# Main.net
KiCad netlist of a schematic drawn in Altium Designer
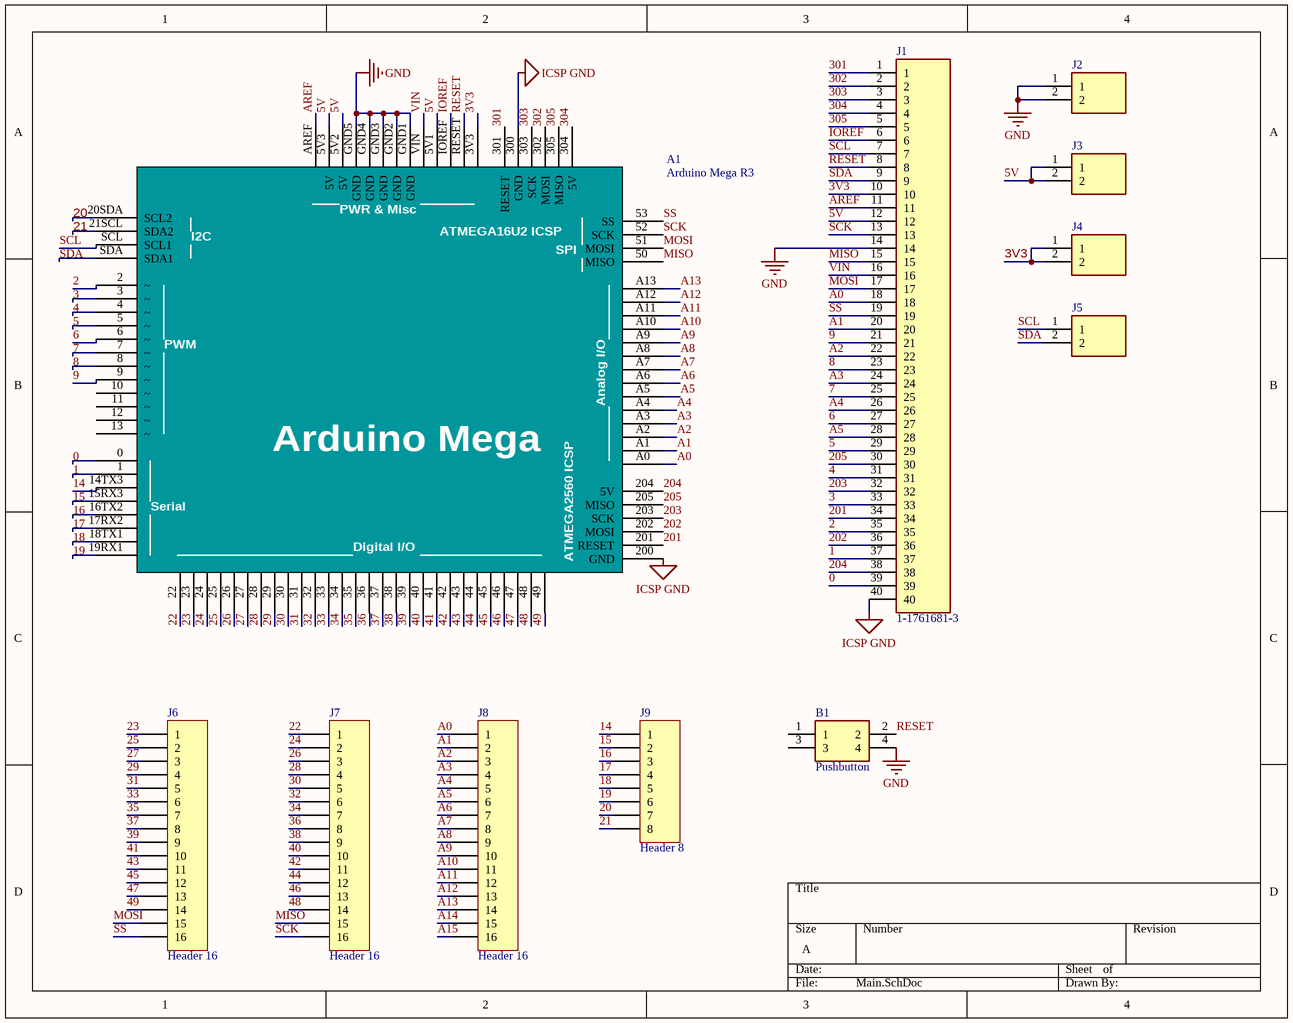
[diagram p0: Main.SchDoc]

(export (version "E")
  (design (tool "Eeschema 10.0.6"))
  (components
    (comp (ref "A1")
      (value "Arduino Mega R3")
      (footprint "Arduino Mega")
      (libsource (lib "Detailed Arduino") (part "Arduino Mega"))
    )
    (comp (ref "B1")
      (value "Pushbutton")
      (footprint "SamacSys:FSM4JH")
      (description "Switch")
      (fields
        (field (name "MANUFACTURER_PART_NUMBER") "FSM2JAH")
        (field (name "MOUSER PART NUMBER") "506-FSM2JAH")
      )
      (libsource (lib "SamacSys") (part "Pushbutton"))
    )
    (comp (ref "J1")
      (value "1-1761681-3")
      (footprint "TE_1-1761681-3")
      (description "IDC LOW PRO HDR 50P VERT HT BLACK")
      (libsource (lib "Molex 40pin Connector") (part "1-1761681-3"))
    )
    (comp (ref "J2")
      (value "TB002-500-02BE")
      (footprint "SamacSys:TB00250002BE")
      (description "Connector")
      (fields (field (name "MOUSER PART NUMBER") "490-TB002-500-02BE"))
      (libsource (lib "SamacSys") (part "TB002-500-02BE"))
    )
    (comp (ref "J3")
      (value "TB002-500-02BE")
      (footprint "SamacSys:TB00250002BE")
      (description "Connector")
      (fields (field (name "MOUSER PART NUMBER") "490-TB002-500-02BE"))
      (libsource (lib "SamacSys") (part "TB002-500-02BE"))
    )
    (comp (ref "J4")
      (value "TB002-500-02BE")
      (footprint "SamacSys:TB00250002BE")
      (description "Connector")
      (fields (field (name "MOUSER PART NUMBER") "490-TB002-500-02BE"))
      (libsource (lib "SamacSys") (part "TB002-500-02BE"))
    )
    (comp (ref "J5")
      (value "TB002-500-02BE")
      (footprint "SamacSys:TB00250002BE")
      (description "Connector")
      (fields (field (name "MOUSER PART NUMBER") "490-TB002-500-02BE"))
      (libsource (lib "SamacSys") (part "TB002-500-02BE"))
    )
    (comp (ref "J6")
      (value "Header 16")
      (footprint "HDR1X16")
      (description "Header, 16-Pin")
      (fields (field (name "PUBLISHER") "Altium Limited"))
      (libsource (lib "Miscellaneous Connectors") (part "Header 16"))
    )
    (comp (ref "J7")
      (value "Header 16")
      (footprint "HDR1X16")
      (description "Header, 16-Pin")
      (fields (field (name "PUBLISHER") "Altium Limited"))
      (libsource (lib "Miscellaneous Connectors") (part "Header 16"))
    )
    (comp (ref "J8")
      (value "Header 16")
      (footprint "HDR1X16")
      (description "Header, 16-Pin")
      (fields (field (name "PUBLISHER") "Altium Limited"))
      (libsource (lib "Miscellaneous Connectors") (part "Header 16"))
    )
    (comp (ref "J9")
      (value "Header 8")
      (footprint "HDR1X8")
      (description "Header, 8-Pin")
      (fields (field (name "PUBLISHER") "Altium Limited"))
      (libsource (lib "Miscellaneous Connectors") (part "Header 8"))
    )
  )
  (nets
    (net (code "1") (name "/0") (class "Default")
      (node (ref "A1") (pin "0") (pintype "power_in"))
      (node (ref "J1") (pin "39") (pinfunction "39_39") (pintype "passive"))
    )
    (net (code "2") (name "/1") (class "Default")
      (node (ref "A1") (pin "1") (pintype "power_in"))
      (node (ref "J1") (pin "37") (pinfunction "37_37") (pintype "passive"))
    )
    (net (code "3") (name "/2") (class "Default")
      (node (ref "A1") (pin "2") (pinfunction "~_2") (pintype "power_in"))
      (node (ref "J1") (pin "35") (pinfunction "35_35") (pintype "passive"))
    )
    (net (code "4") (name "/3") (class "Default")
      (node (ref "A1") (pin "3") (pinfunction "~_3") (pintype "power_in"))
      (node (ref "J1") (pin "33") (pinfunction "33_33") (pintype "passive"))
    )
    (net (code "5") (name "/3V3") (class "Default")
      (node (ref "A1") (pin "3V3") (pintype "power_in"))
      (node (ref "J1") (pin "10") (pinfunction "10_10") (pintype "passive"))
      (node (ref "J4") (pin "1") (pinfunction "1_1") (pintype "passive"))
      (node (ref "J4") (pin "2") (pinfunction "2_2") (pintype "passive"))
    )
    (net (code "6") (name "/4") (class "Default")
      (node (ref "A1") (pin "4") (pinfunction "~_4") (pintype "power_in"))
      (node (ref "J1") (pin "31") (pinfunction "31_31") (pintype "passive"))
    )
    (net (code "7") (name "/5") (class "Default")
      (node (ref "A1") (pin "5") (pinfunction "~_5") (pintype "power_in"))
      (node (ref "J1") (pin "29") (pinfunction "29_29") (pintype "passive"))
    )
    (net (code "8") (name "/5V") (class "Default")
      (node (ref "A1") (pin "5V1") (pintype "power_in"))
      (node (ref "A1") (pin "5V2") (pinfunction "5V_5V2") (pintype "power_in"))
      (node (ref "A1") (pin "5V3") (pinfunction "5V_5V3") (pintype "power_in"))
      (node (ref "J1") (pin "12") (pinfunction "12_12") (pintype "passive"))
      (node (ref "J3") (pin "1") (pinfunction "1_1") (pintype "passive"))
      (node (ref "J3") (pin "2") (pinfunction "2_2") (pintype "passive"))
    )
    (net (code "9") (name "/6") (class "Default")
      (node (ref "A1") (pin "6") (pinfunction "~_6") (pintype "power_in"))
      (node (ref "J1") (pin "27") (pinfunction "27_27") (pintype "passive"))
    )
    (net (code "10") (name "/7") (class "Default")
      (node (ref "A1") (pin "7") (pinfunction "~_7") (pintype "power_in"))
      (node (ref "J1") (pin "25") (pinfunction "25_25") (pintype "passive"))
    )
    (net (code "11") (name "/8") (class "Default")
      (node (ref "A1") (pin "8") (pinfunction "~_8") (pintype "power_in"))
      (node (ref "J1") (pin "23") (pinfunction "23_23") (pintype "passive"))
    )
    (net (code "12") (name "/9") (class "Default")
      (node (ref "A1") (pin "9") (pinfunction "~_9") (pintype "power_in"))
      (node (ref "J1") (pin "21") (pinfunction "21_21") (pintype "passive"))
    )
    (net (code "13") (name "/14") (class "Default")
      (node (ref "A1") (pin "14TX3") (pintype "power_in"))
      (node (ref "J9") (pin "1") (pinfunction "1_1") (pintype "passive"))
    )
    (net (code "14") (name "/15") (class "Default")
      (node (ref "A1") (pin "15RX3") (pintype "power_in"))
      (node (ref "J9") (pin "2") (pinfunction "2_2") (pintype "passive"))
    )
    (net (code "15") (name "/16") (class "Default")
      (node (ref "A1") (pin "16TX2") (pintype "power_in"))
      (node (ref "J9") (pin "3") (pinfunction "3_3") (pintype "passive"))
    )
    (net (code "16") (name "/17") (class "Default")
      (node (ref "A1") (pin "17RX2") (pintype "power_in"))
      (node (ref "J9") (pin "4") (pinfunction "4_4") (pintype "passive"))
    )
    (net (code "17") (name "/18") (class "Default")
      (node (ref "A1") (pin "18TX1") (pintype "power_in"))
      (node (ref "J9") (pin "5") (pinfunction "5_5") (pintype "passive"))
    )
    (net (code "18") (name "/19") (class "Default")
      (node (ref "A1") (pin "19RX1") (pintype "power_in"))
      (node (ref "J9") (pin "6") (pinfunction "6_6") (pintype "passive"))
    )
    (net (code "19") (name "/20") (class "Default")
      (node (ref "A1") (pin "20SDA") (pinfunction "SCL2_20SDA") (pintype "power_in"))
      (node (ref "J9") (pin "7") (pinfunction "7_7") (pintype "passive"))
    )
    (net (code "20") (name "/21") (class "Default")
      (node (ref "A1") (pin "21SCL") (pinfunction "SDA2_21SCL") (pintype "power_in"))
      (node (ref "J9") (pin "8") (pinfunction "8_8") (pintype "passive"))
    )
    (net (code "21") (name "/22") (class "Default")
      (node (ref "A1") (pin "22") (pintype "power_in"))
      (node (ref "J7") (pin "1") (pinfunction "1_1") (pintype "passive"))
    )
    (net (code "22") (name "/23") (class "Default")
      (node (ref "A1") (pin "23") (pintype "power_in"))
      (node (ref "J6") (pin "1") (pinfunction "1_1") (pintype "passive"))
    )
    (net (code "23") (name "/24") (class "Default")
      (node (ref "A1") (pin "24") (pintype "power_in"))
      (node (ref "J7") (pin "2") (pinfunction "2_2") (pintype "passive"))
    )
    (net (code "24") (name "/25") (class "Default")
      (node (ref "A1") (pin "25") (pintype "power_in"))
      (node (ref "J6") (pin "2") (pinfunction "2_2") (pintype "passive"))
    )
    (net (code "25") (name "/26") (class "Default")
      (node (ref "A1") (pin "26") (pintype "power_in"))
      (node (ref "J7") (pin "3") (pinfunction "3_3") (pintype "passive"))
    )
    (net (code "26") (name "/27") (class "Default")
      (node (ref "A1") (pin "27") (pintype "power_in"))
      (node (ref "J6") (pin "3") (pinfunction "3_3") (pintype "passive"))
    )
    (net (code "27") (name "/28") (class "Default")
      (node (ref "A1") (pin "28") (pintype "power_in"))
      (node (ref "J7") (pin "4") (pinfunction "4_4") (pintype "passive"))
    )
    (net (code "28") (name "/29") (class "Default")
      (node (ref "A1") (pin "29") (pintype "power_in"))
      (node (ref "J6") (pin "4") (pinfunction "4_4") (pintype "passive"))
    )
    (net (code "29") (name "/30") (class "Default")
      (node (ref "A1") (pin "30") (pintype "power_in"))
      (node (ref "J7") (pin "5") (pinfunction "5_5") (pintype "passive"))
    )
    (net (code "30") (name "/31") (class "Default")
      (node (ref "A1") (pin "31") (pintype "power_in"))
      (node (ref "J6") (pin "5") (pinfunction "5_5") (pintype "passive"))
    )
    (net (code "31") (name "/32") (class "Default")
      (node (ref "A1") (pin "32") (pintype "power_in"))
      (node (ref "J7") (pin "6") (pinfunction "6_6") (pintype "passive"))
    )
    (net (code "32") (name "/33") (class "Default")
      (node (ref "A1") (pin "33") (pintype "power_in"))
      (node (ref "J6") (pin "6") (pinfunction "6_6") (pintype "passive"))
    )
    (net (code "33") (name "/34") (class "Default")
      (node (ref "A1") (pin "34") (pintype "power_in"))
      (node (ref "J7") (pin "7") (pinfunction "7_7") (pintype "passive"))
    )
    (net (code "34") (name "/35") (class "Default")
      (node (ref "A1") (pin "35") (pintype "power_in"))
      (node (ref "J6") (pin "7") (pinfunction "7_7") (pintype "passive"))
    )
    (net (code "35") (name "/36") (class "Default")
      (node (ref "A1") (pin "36") (pintype "power_in"))
      (node (ref "J7") (pin "8") (pinfunction "8_8") (pintype "passive"))
    )
    (net (code "36") (name "/37") (class "Default")
      (node (ref "A1") (pin "37") (pintype "power_in"))
      (node (ref "J6") (pin "8") (pinfunction "8_8") (pintype "passive"))
    )
    (net (code "37") (name "/38") (class "Default")
      (node (ref "A1") (pin "38") (pintype "power_in"))
      (node (ref "J7") (pin "9") (pinfunction "9_9") (pintype "passive"))
    )
    (net (code "38") (name "/39") (class "Default")
      (node (ref "A1") (pin "39") (pintype "power_in"))
      (node (ref "J6") (pin "9") (pinfunction "9_9") (pintype "passive"))
    )
    (net (code "39") (name "/40") (class "Default")
      (node (ref "A1") (pin "40") (pintype "power_in"))
      (node (ref "J7") (pin "10") (pinfunction "10_10") (pintype "passive"))
    )
    (net (code "40") (name "/41") (class "Default")
      (node (ref "A1") (pin "41") (pintype "power_in"))
      (node (ref "J6") (pin "10") (pinfunction "10_10") (pintype "passive"))
    )
    (net (code "41") (name "/42") (class "Default")
      (node (ref "A1") (pin "42") (pintype "power_in"))
      (node (ref "J7") (pin "11") (pinfunction "11_11") (pintype "passive"))
    )
    (net (code "42") (name "/43") (class "Default")
      (node (ref "A1") (pin "43") (pintype "power_in"))
      (node (ref "J6") (pin "11") (pinfunction "11_11") (pintype "passive"))
    )
    (net (code "43") (name "/44") (class "Default")
      (node (ref "A1") (pin "44") (pintype "power_in"))
      (node (ref "J7") (pin "12") (pinfunction "12_12") (pintype "passive"))
    )
    (net (code "44") (name "/45") (class "Default")
      (node (ref "A1") (pin "45") (pintype "power_in"))
      (node (ref "J6") (pin "12") (pinfunction "12_12") (pintype "passive"))
    )
    (net (code "45") (name "/46") (class "Default")
      (node (ref "A1") (pin "46") (pintype "power_in"))
      (node (ref "J7") (pin "13") (pinfunction "13_13") (pintype "passive"))
    )
    (net (code "46") (name "/47") (class "Default")
      (node (ref "A1") (pin "47") (pintype "power_in"))
      (node (ref "J6") (pin "13") (pinfunction "13_13") (pintype "passive"))
    )
    (net (code "47") (name "/48") (class "Default")
      (node (ref "A1") (pin "48") (pintype "power_in"))
      (node (ref "J7") (pin "14") (pinfunction "14_14") (pintype "passive"))
    )
    (net (code "48") (name "/49") (class "Default")
      (node (ref "A1") (pin "49") (pintype "power_in"))
      (node (ref "J6") (pin "14") (pinfunction "14_14") (pintype "passive"))
    )
    (net (code "49") (name "/201") (class "Default")
      (node (ref "A1") (pin "201") (pinfunction "RESET_201") (pintype "power_in"))
      (node (ref "J1") (pin "34") (pinfunction "34_34") (pintype "passive"))
    )
    (net (code "50") (name "/202") (class "Default")
      (node (ref "A1") (pin "202") (pinfunction "MOSI_202") (pintype "power_in"))
      (node (ref "J1") (pin "36") (pinfunction "36_36") (pintype "passive"))
    )
    (net (code "51") (name "/203") (class "Default")
      (node (ref "A1") (pin "203") (pinfunction "SCK_203") (pintype "power_in"))
      (node (ref "J1") (pin "32") (pinfunction "32_32") (pintype "passive"))
    )
    (net (code "52") (name "/204") (class "Default")
      (node (ref "A1") (pin "204") (pinfunction "5V_204") (pintype "power_in"))
      (node (ref "J1") (pin "38") (pinfunction "38_38") (pintype "passive"))
    )
    (net (code "53") (name "/205") (class "Default")
      (node (ref "A1") (pin "205") (pinfunction "MISO_205") (pintype "power_in"))
      (node (ref "J1") (pin "30") (pinfunction "30_30") (pintype "passive"))
    )
    (net (code "54") (name "/301") (class "Default")
      (node (ref "A1") (pin "301") (pinfunction "RESET_301") (pintype "power_in"))
      (node (ref "J1") (pin "1") (pinfunction "1_1") (pintype "passive"))
    )
    (net (code "55") (name "/302") (class "Default")
      (node (ref "A1") (pin "302") (pinfunction "MOSI_302") (pintype "power_in"))
      (node (ref "J1") (pin "2") (pinfunction "2_2") (pintype "passive"))
    )
    (net (code "56") (name "/303") (class "Default")
      (node (ref "A1") (pin "303") (pinfunction "SCK_303") (pintype "power_in"))
      (node (ref "J1") (pin "3") (pinfunction "3_3") (pintype "passive"))
    )
    (net (code "57") (name "/304") (class "Default")
      (node (ref "A1") (pin "304") (pinfunction "5V_304") (pintype "power_in"))
      (node (ref "J1") (pin "4") (pinfunction "4_4") (pintype "passive"))
    )
    (net (code "58") (name "/305") (class "Default")
      (node (ref "A1") (pin "305") (pinfunction "MISO_305") (pintype "power_in"))
      (node (ref "J1") (pin "5") (pinfunction "5_5") (pintype "passive"))
    )
    (net (code "59") (name "/A0") (class "Default")
      (node (ref "A1") (pin "A0") (pintype "power_in"))
      (node (ref "J1") (pin "18") (pinfunction "18_18") (pintype "passive"))
      (node (ref "J8") (pin "1") (pinfunction "1_1") (pintype "passive"))
    )
    (net (code "60") (name "/A1") (class "Default")
      (node (ref "A1") (pin "A1") (pintype "power_in"))
      (node (ref "J1") (pin "20") (pinfunction "20_20") (pintype "passive"))
      (node (ref "J8") (pin "2") (pinfunction "2_2") (pintype "passive"))
    )
    (net (code "61") (name "/A2") (class "Default")
      (node (ref "A1") (pin "A2") (pintype "power_in"))
      (node (ref "J1") (pin "22") (pinfunction "22_22") (pintype "passive"))
      (node (ref "J8") (pin "3") (pinfunction "3_3") (pintype "passive"))
    )
    (net (code "62") (name "/A3") (class "Default")
      (node (ref "A1") (pin "A3") (pintype "power_in"))
      (node (ref "J1") (pin "24") (pinfunction "24_24") (pintype "passive"))
      (node (ref "J8") (pin "4") (pinfunction "4_4") (pintype "passive"))
    )
    (net (code "63") (name "/A4") (class "Default")
      (node (ref "A1") (pin "A4") (pintype "power_in"))
      (node (ref "J1") (pin "26") (pinfunction "26_26") (pintype "passive"))
      (node (ref "J8") (pin "5") (pinfunction "5_5") (pintype "passive"))
    )
    (net (code "64") (name "/A5") (class "Default")
      (node (ref "A1") (pin "A5") (pintype "power_in"))
      (node (ref "J1") (pin "28") (pinfunction "28_28") (pintype "passive"))
      (node (ref "J8") (pin "6") (pinfunction "6_6") (pintype "passive"))
    )
    (net (code "65") (name "/A6") (class "Default")
      (node (ref "A1") (pin "A6") (pintype "power_in"))
      (node (ref "J8") (pin "7") (pinfunction "7_7") (pintype "passive"))
    )
    (net (code "66") (name "/A7") (class "Default")
      (node (ref "A1") (pin "A7") (pintype "power_in"))
      (node (ref "J8") (pin "8") (pinfunction "8_8") (pintype "passive"))
    )
    (net (code "67") (name "/A8") (class "Default")
      (node (ref "A1") (pin "A8") (pintype "power_in"))
      (node (ref "J8") (pin "9") (pinfunction "9_9") (pintype "passive"))
    )
    (net (code "68") (name "/A9") (class "Default")
      (node (ref "A1") (pin "A9") (pintype "power_in"))
      (node (ref "J8") (pin "10") (pinfunction "10_10") (pintype "passive"))
    )
    (net (code "69") (name "/A10") (class "Default")
      (node (ref "A1") (pin "A10") (pintype "power_in"))
      (node (ref "J8") (pin "11") (pinfunction "11_11") (pintype "passive"))
    )
    (net (code "70") (name "/A11") (class "Default")
      (node (ref "A1") (pin "A11") (pintype "power_in"))
      (node (ref "J8") (pin "12") (pinfunction "12_12") (pintype "passive"))
    )
    (net (code "71") (name "/A12") (class "Default")
      (node (ref "A1") (pin "A12") (pintype "power_in"))
      (node (ref "J8") (pin "13") (pinfunction "13_13") (pintype "passive"))
    )
    (net (code "72") (name "/A13") (class "Default")
      (node (ref "A1") (pin "A13") (pintype "power_in"))
      (node (ref "J8") (pin "14") (pinfunction "14_14") (pintype "passive"))
    )
    (net (code "73") (name "/A14") (class "Default")
      (node (ref "J8") (pin "15") (pinfunction "15_15") (pintype "passive"))
    )
    (net (code "74") (name "/A15") (class "Default")
      (node (ref "J8") (pin "16") (pinfunction "16_16") (pintype "passive"))
    )
    (net (code "75") (name "/AREF") (class "Default")
      (node (ref "A1") (pin "AREF") (pintype "power_in"))
      (node (ref "J1") (pin "11") (pinfunction "11_11") (pintype "passive"))
    )
    (net (code "76") (name "/IOREF") (class "Default")
      (node (ref "A1") (pin "IOREF") (pintype "power_in"))
      (node (ref "J1") (pin "6") (pinfunction "6_6") (pintype "passive"))
    )
    (net (code "77") (name "/MISO") (class "Default")
      (node (ref "A1") (pin "50") (pinfunction "MISO_50") (pintype "power_in"))
      (node (ref "J1") (pin "15") (pinfunction "15_15") (pintype "passive"))
      (node (ref "J7") (pin "15") (pinfunction "15_15") (pintype "passive"))
    )
    (net (code "78") (name "/MOSI") (class "Default")
      (node (ref "A1") (pin "51") (pinfunction "MOSI_51") (pintype "power_in"))
      (node (ref "J1") (pin "17") (pinfunction "17_17") (pintype "passive"))
      (node (ref "J6") (pin "15") (pinfunction "15_15") (pintype "passive"))
    )
    (net (code "79") (name "/RESET") (class "Default")
      (node (ref "A1") (pin "RESET") (pintype "power_in"))
      (node (ref "B1") (pin "2") (pinfunction "2_2") (pintype "passive"))
      (node (ref "J1") (pin "8") (pinfunction "8_8") (pintype "passive"))
    )
    (net (code "80") (name "/SCK") (class "Default")
      (node (ref "A1") (pin "52") (pinfunction "SCK_52") (pintype "power_in"))
      (node (ref "J1") (pin "13") (pinfunction "13_13") (pintype "passive"))
      (node (ref "J7") (pin "16") (pinfunction "16_16") (pintype "passive"))
    )
    (net (code "81") (name "/SCL") (class "Default")
      (node (ref "A1") (pin "SCL") (pinfunction "SCL1_SCL") (pintype "power_in"))
      (node (ref "J1") (pin "7") (pinfunction "7_7") (pintype "passive"))
      (node (ref "J5") (pin "1") (pinfunction "1_1") (pintype "passive"))
    )
    (net (code "82") (name "/SDA") (class "Default")
      (node (ref "A1") (pin "SDA") (pinfunction "SDA1_SDA") (pintype "power_in"))
      (node (ref "J1") (pin "9") (pinfunction "9_9") (pintype "passive"))
      (node (ref "J5") (pin "2") (pinfunction "2_2") (pintype "passive"))
    )
    (net (code "83") (name "/SS") (class "Default")
      (node (ref "A1") (pin "53") (pinfunction "SS_53") (pintype "power_in"))
      (node (ref "J1") (pin "19") (pinfunction "19_19") (pintype "passive"))
      (node (ref "J6") (pin "16") (pinfunction "16_16") (pintype "passive"))
    )
    (net (code "84") (name "/VIN") (class "Default")
      (node (ref "A1") (pin "VIN") (pintype "power_in"))
      (node (ref "J1") (pin "16") (pinfunction "16_16") (pintype "passive"))
    )
    (net (code "85") (name "GND") (class "Default")
      (node (ref "A1") (pin "GND1") (pinfunction "GND_GND1") (pintype "power_in"))
      (node (ref "A1") (pin "GND2") (pinfunction "GND_GND2") (pintype "power_in"))
      (node (ref "A1") (pin "GND3") (pinfunction "GND_GND3") (pintype "power_in"))
      (node (ref "A1") (pin "GND4") (pinfunction "GND_GND4") (pintype "power_in"))
      (node (ref "A1") (pin "GND5") (pinfunction "GND_GND5") (pintype "power_in"))
      (node (ref "B1") (pin "4") (pinfunction "4_4") (pintype "passive"))
      (node (ref "J1") (pin "14") (pinfunction "14_14") (pintype "passive"))
      (node (ref "J2") (pin "1") (pinfunction "1_1") (pintype "passive"))
      (node (ref "J2") (pin "2") (pinfunction "2_2") (pintype "passive"))
    )
    (net (code "86") (name "ICSP GND") (class "Default")
      (node (ref "A1") (pin "200") (pinfunction "GND_200") (pintype "power_in"))
      (node (ref "A1") (pin "300") (pinfunction "GND_300") (pintype "power_in"))
      (node (ref "J1") (pin "40") (pinfunction "40_40") (pintype "passive"))
    )
    (net (code "87") (name "unconnected-(A1-~-Pad10)") (class "Default")
      (node (ref "A1") (pin "10") (pinfunction "~_10") (pintype "power_in"))
    )
    (net (code "88") (name "unconnected-(A1-~-Pad11)") (class "Default")
      (node (ref "A1") (pin "11") (pinfunction "~_11") (pintype "power_in"))
    )
    (net (code "89") (name "unconnected-(A1-~-Pad12)") (class "Default")
      (node (ref "A1") (pin "12") (pinfunction "~_12") (pintype "power_in"))
    )
    (net (code "90") (name "unconnected-(A1-~-Pad13)") (class "Default")
      (node (ref "A1") (pin "13") (pinfunction "~_13") (pintype "power_in"))
    )
    (net (code "91") (name "unconnected-(B1-Pad1)") (class "Default")
      (node (ref "B1") (pin "1") (pinfunction "1_1") (pintype "passive"))
    )
    (net (code "92") (name "unconnected-(B1-Pad3)") (class "Default")
      (node (ref "B1") (pin "3") (pinfunction "3_3") (pintype "passive"))
    )
  )
)
